# myBusToUEXT.net
KiCad netlist of a schematic drawn in EAGLE
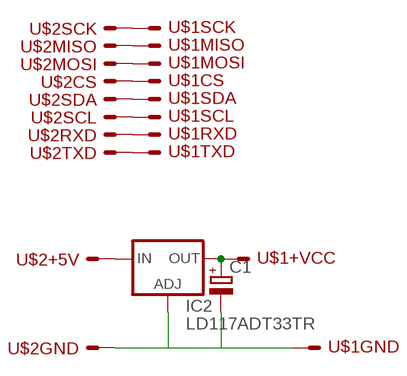
[diagram p0: schematic, sheet 1]

(export (version "E")
  (design (tool "Eeschema 10.0.6"))
  (components
    (comp (ref "C1")
      (value "CPOL-EUE2.5-5")
      (footprint "eagle-import:E2,5-5")
      (libsource (lib "eagle-import") (part "CPOL-EUE2.5-5"))
    )
    (comp (ref "IC2")
      (value "LD117ADT33TR")
      (footprint "eagle-import:DPACK")
      (libsource (lib "eagle-import") (part "LD117A?DT33TR"))
    )
    (comp (ref "U$1")
      (value "SPI_BUS2")
      (footprint "eagle-import:SPI_BUS2")
      (libsource (lib "eagle-import") (part "SPI_BUS2"))
    )
    (comp (ref "U$2")
      (value "SPI_BUS")
      (footprint "eagle-import:SPI_BUS")
      (libsource (lib "eagle-import") (part "SPI_BUS"))
    )
  )
  (nets
    (net (code "1") (name "Net-(IC2-ADJ)") (class "Default")
      (node (ref "C1") (pin "-") (pinfunction "-_-") (pintype "passive"))
      (node (ref "IC2") (pin "1") (pinfunction "ADJ_1") (pintype "input"))
      (node (ref "U$1") (pin "GND") (pinfunction "S_GND") (pintype "passive"))
      (node (ref "U$2") (pin "GND") (pinfunction "S_GND") (pintype "passive"))
    )
    (net (code "2") (name "Net-(IC2-IN)") (class "Default")
      (node (ref "IC2") (pin "3") (pinfunction "IN_3") (pintype "input"))
      (node (ref "U$2") (pin "+5V") (pinfunction "S_+5V") (pintype "passive"))
    )
    (net (code "3") (name "Net-(IC2-OUT)") (class "Default")
      (node (ref "C1") (pin "+") (pinfunction "+_+") (pintype "passive"))
      (node (ref "IC2") (pin "4") (pinfunction "OUT_4") (pintype "passive"))
      (node (ref "U$1") (pin "+VCC") (pinfunction "S_+VCC") (pintype "passive"))
    )
    (net (code "4") (name "Net-(U$1B-S)") (class "Default")
      (node (ref "U$1") (pin "CS") (pinfunction "S_CS") (pintype "passive"))
      (node (ref "U$2") (pin "CS") (pinfunction "S_CS") (pintype "passive"))
    )
    (net (code "5") (name "Net-(U$1D-S)") (class "Default")
      (node (ref "U$1") (pin "MISO") (pinfunction "S_MISO") (pintype "passive"))
      (node (ref "U$2") (pin "MISO") (pinfunction "S_MISO") (pintype "passive"))
    )
    (net (code "6") (name "Net-(U$1E-S)") (class "Default")
      (node (ref "U$1") (pin "MOSI") (pinfunction "S_MOSI") (pintype "passive"))
      (node (ref "U$2") (pin "MOSI") (pinfunction "S_MOSI") (pintype "passive"))
    )
    (net (code "7") (name "Net-(U$1F-S)") (class "Default")
      (node (ref "U$1") (pin "GPIO/RXD") (pinfunction "S_GPIO/RXD") (pintype "passive"))
      (node (ref "U$2") (pin "RXD") (pinfunction "S_RXD") (pintype "passive"))
    )
    (net (code "8") (name "Net-(U$1G-S)") (class "Default")
      (node (ref "U$1") (pin "SCK") (pinfunction "S_SCK") (pintype "passive"))
      (node (ref "U$2") (pin "SCK") (pinfunction "S_SCK") (pintype "passive"))
    )
    (net (code "9") (name "Net-(U$1H-S)") (class "Default")
      (node (ref "U$1") (pin "RST/SCL") (pinfunction "S_RST/SCL") (pintype "passive"))
      (node (ref "U$2") (pin "SCL") (pinfunction "S_SCL") (pintype "passive"))
    )
    (net (code "10") (name "Net-(U$1I-S)") (class "Default")
      (node (ref "U$1") (pin "INT/SDA") (pinfunction "S_INT/SDA") (pintype "passive"))
      (node (ref "U$2") (pin "SDA") (pinfunction "S_SDA") (pintype "passive"))
    )
    (net (code "11") (name "Net-(U$1J-S)") (class "Default")
      (node (ref "U$1") (pin "TXD") (pinfunction "S_TXD") (pintype "passive"))
      (node (ref "U$2") (pin "TXD") (pinfunction "S_TXD") (pintype "passive"))
    )
  )
)
